# AAS_module_MCU-rev1_2.net
KiCad netlist of a schematic drawn in Altium Designer
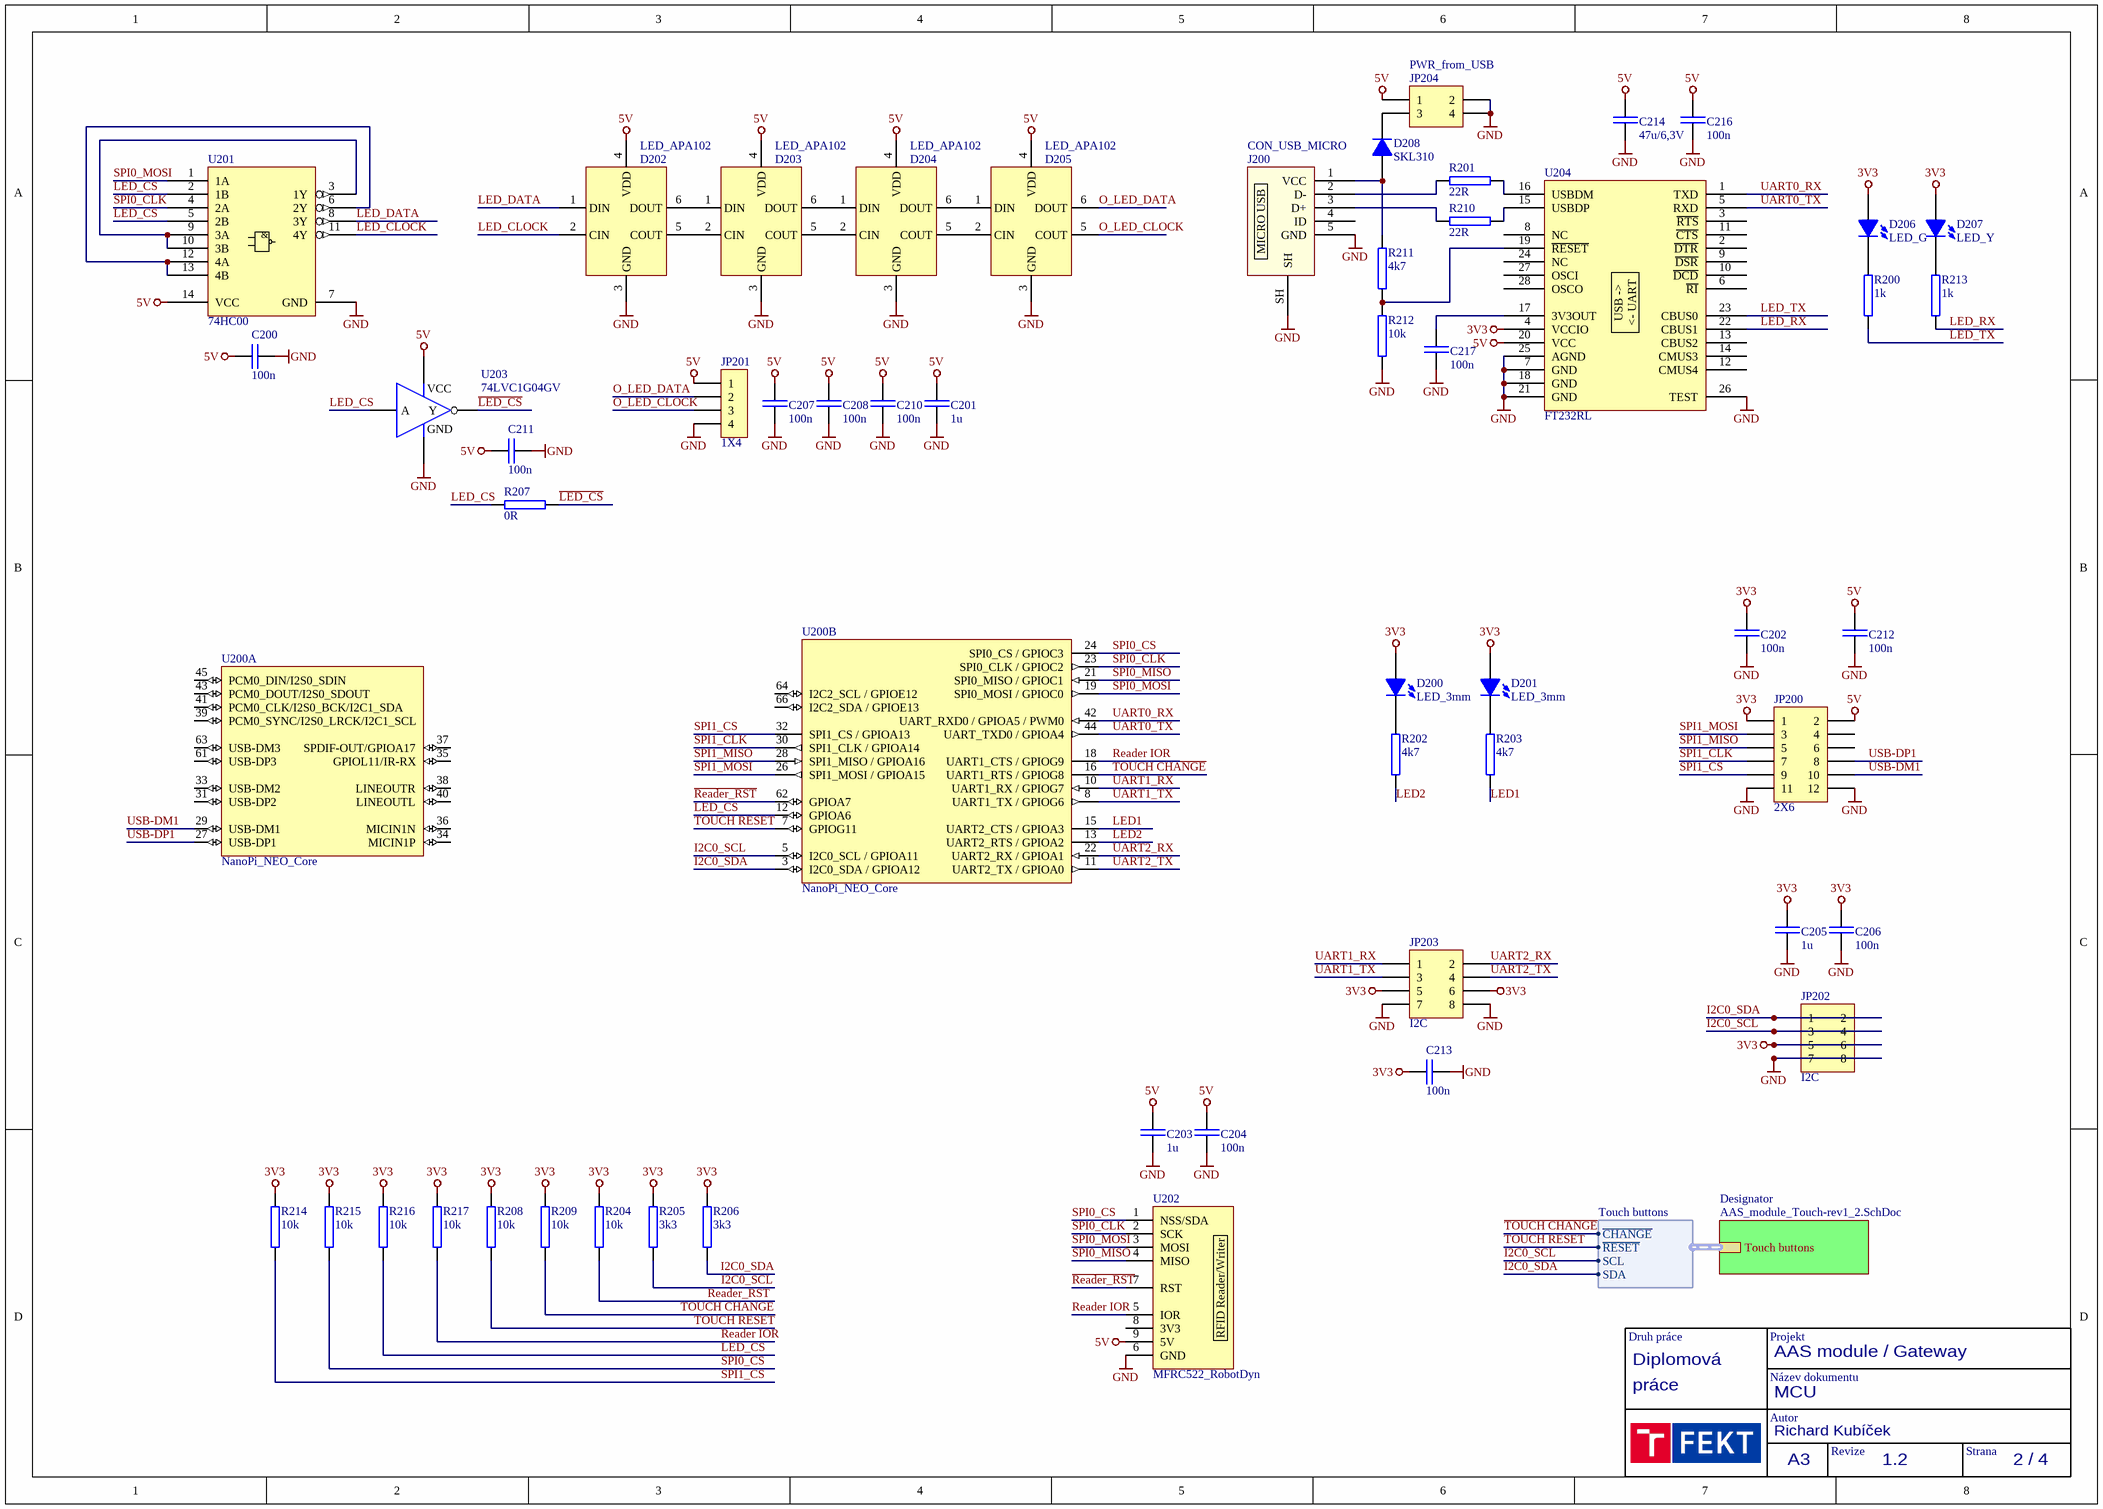
[diagram p0: AAS_module_MCU-rev1_2.SchDoc]

(export (version "E")
  (design (tool "Eeschema 10.0.6"))
  (components
    (comp (ref "C200")
      (value "100n")
      (footprint "C0603")
      (description "Capacitor SMD 0603")
      (libsource (lib "SmartSys") (part "C_0603"))
    )
    (comp (ref "C201")
      (value "1u")
      (footprint "C0603")
      (description "Capacitor SMD 0603")
      (libsource (lib "SmartSys") (part "C_0603"))
    )
    (comp (ref "C202")
      (value "100n")
      (footprint "C0603")
      (description "Capacitor SMD 0603")
      (libsource (lib "SmartSys") (part "C_0603"))
    )
    (comp (ref "C203")
      (value "1u")
      (footprint "C0603")
      (description "Capacitor SMD 0603")
      (libsource (lib "SmartSys") (part "C_0603"))
    )
    (comp (ref "C204")
      (value "100n")
      (footprint "C0603")
      (description "Capacitor SMD 0603")
      (libsource (lib "SmartSys") (part "C_0603"))
    )
    (comp (ref "C205")
      (value "1u")
      (footprint "C0603")
      (description "Capacitor SMD 0603")
      (libsource (lib "SmartSys") (part "C_0603"))
    )
    (comp (ref "C206")
      (value "100n")
      (footprint "C0603")
      (description "Capacitor SMD 0603")
      (libsource (lib "SmartSys") (part "C_0603"))
    )
    (comp (ref "C207")
      (value "100n")
      (footprint "C0603")
      (description "Capacitor SMD 0603")
      (libsource (lib "SmartSys") (part "C_0603"))
    )
    (comp (ref "C208")
      (value "100n")
      (footprint "C0603")
      (description "Capacitor SMD 0603")
      (libsource (lib "SmartSys") (part "C_0603"))
    )
    (comp (ref "C210")
      (value "100n")
      (footprint "C0603")
      (description "Capacitor SMD 0603")
      (libsource (lib "SmartSys") (part "C_0603"))
    )
    (comp (ref "C211")
      (value "100n")
      (footprint "C0603")
      (description "Capacitor SMD 0603")
      (libsource (lib "SmartSys") (part "C_0603"))
    )
    (comp (ref "C212")
      (value "100n")
      (footprint "C0603")
      (description "Capacitor SMD 0603")
      (libsource (lib "SmartSys") (part "C_0603"))
    )
    (comp (ref "C213")
      (value "100n")
      (footprint "C0603")
      (description "Capacitor SMD 0603")
      (libsource (lib "SmartSys") (part "C_0603"))
    )
    (comp (ref "C214")
      (value "47u/6,3V")
      (footprint "C1206")
      (description "Capacitor SMD 1206")
      (libsource (lib "SmartSys") (part "C_1206"))
    )
    (comp (ref "C216")
      (value "100n")
      (footprint "C0603")
      (description "Capacitor SMD 0603")
      (libsource (lib "SmartSys") (part "C_0603"))
    )
    (comp (ref "C217")
      (value "100n")
      (footprint "C0603")
      (description "Capacitor SMD 0603")
      (libsource (lib "SmartSys") (part "C_0603"))
    )
    (comp (ref "D200")
      (value "LED_3mm")
      (footprint "LED_THT_3MM_P2.5_GREEN")
      (description "LED 3mm")
      (libsource (lib "SmartSys") (part "LED_3mm"))
    )
    (comp (ref "D201")
      (value "LED_3mm")
      (footprint "LED_THT_3MM_P2.5_GREEN")
      (description "LED 3mm")
      (libsource (lib "SmartSys") (part "LED_3mm"))
    )
    (comp (ref "D202")
      (value "LED_APA102")
      (footprint "APA102")
      (description "Intelligent control LED integrated light source")
      (libsource (lib "my_parts") (part "LED_APA102"))
    )
    (comp (ref "D203")
      (value "LED_APA102")
      (footprint "APA102")
      (description "Intelligent control LED integrated light source")
      (libsource (lib "my_parts") (part "LED_APA102"))
    )
    (comp (ref "D204")
      (value "LED_APA102")
      (footprint "APA102")
      (description "Intelligent control LED integrated light source")
      (libsource (lib "my_parts") (part "LED_APA102"))
    )
    (comp (ref "D205")
      (value "LED_APA102")
      (footprint "APA102")
      (description "Intelligent control LED integrated light source")
      (libsource (lib "my_parts") (part "LED_APA102"))
    )
    (comp (ref "D206")
      (value "LED_G")
      (footprint "LED_0603")
      (description "LED SMD 0603")
      (libsource (lib "SmartSys") (part "LED_0603"))
    )
    (comp (ref "D207")
      (value "LED_Y")
      (footprint "LED_0603")
      (description "LED SMD 0603")
      (libsource (lib "SmartSys") (part "LED_0603"))
    )
    (comp (ref "D208")
      (value "SKL310")
      (footprint "SOD123")
      (description "Diode")
      (libsource (lib "SmartSys") (part "1N4007"))
    )
    (comp (ref "J200")
      (value "CON_USB_MICRO")
      (footprint "MICRO USB-B SMD")
      (libsource (lib "SmartSys") (part "CON_USB_MICRO"))
    )
    (comp (ref "JP200")
      (value "2X6")
      (footprint "HDR2x6")
      (description "Header, 12-Pin, Dual row")
      (libsource (lib "SmartSys") (part "Header 2X6"))
    )
    (comp (ref "JP201")
      (value "1X4")
      (footprint "HDR1X4")
      (description "Header, 4-Pin, Single row")
      (libsource (lib "SmartSys") (part "Header 1X4"))
    )
    (comp (ref "JP202")
      (value "I2C")
      (footprint "HDR2X4")
      (description "Header, 8-Pin, Dual row")
      (libsource (lib "SmartSys") (part "Header 2X4"))
    )
    (comp (ref "JP203")
      (value "I2C")
      (footprint "HDR2X4")
      (description "Header, 8-Pin, Dual row")
      (libsource (lib "SmartSys") (part "Header 2X4"))
    )
    (comp (ref "JP204")
      (value "PWR_from_USB")
      (footprint "HDR2X2A")
      (description "Header, 6-Pin, Dual row")
      (libsource (lib "SmartSys") (part "Header 2X2"))
    )
    (comp (ref "R200")
      (value "1k")
      (footprint "R0603")
      (description "Resistor SMD 0603")
      (libsource (lib "SmartSys") (part "R_0603"))
    )
    (comp (ref "R201")
      (value "22R")
      (footprint "R0603")
      (description "Resistor SMD 0603")
      (libsource (lib "SmartSys") (part "R_0603"))
    )
    (comp (ref "R202")
      (value "4k7")
      (footprint "R0603")
      (description "Resistor SMD 0603")
      (libsource (lib "SmartSys") (part "R_0603"))
    )
    (comp (ref "R203")
      (value "4k7")
      (footprint "R0603")
      (description "Resistor SMD 0603")
      (libsource (lib "SmartSys") (part "R_0603"))
    )
    (comp (ref "R204")
      (value "10k")
      (footprint "R0603")
      (description "Resistor SMD 0603")
      (libsource (lib "SmartSys") (part "R_0603"))
    )
    (comp (ref "R205")
      (value "3k3")
      (footprint "R0603")
      (description "Resistor SMD 0603")
      (libsource (lib "SmartSys") (part "R_0603"))
    )
    (comp (ref "R206")
      (value "3k3")
      (footprint "R0603")
      (description "Resistor SMD 0603")
      (libsource (lib "SmartSys") (part "R_0603"))
    )
    (comp (ref "R207")
      (value "0R")
      (footprint "R0603")
      (description "Resistor SMD 0603")
      (libsource (lib "SmartSys") (part "R_0603"))
    )
    (comp (ref "R208")
      (value "10k")
      (footprint "R0603")
      (description "Resistor SMD 0603")
      (libsource (lib "SmartSys") (part "R_0603"))
    )
    (comp (ref "R209")
      (value "10k")
      (footprint "R0603")
      (description "Resistor SMD 0603")
      (libsource (lib "SmartSys") (part "R_0603"))
    )
    (comp (ref "R210")
      (value "22R")
      (footprint "R0603")
      (description "Resistor SMD 0603")
      (libsource (lib "SmartSys") (part "R_0603"))
    )
    (comp (ref "R211")
      (value "4k7")
      (footprint "R0603")
      (description "Resistor SMD 0603")
      (libsource (lib "SmartSys") (part "R_0603"))
    )
    (comp (ref "R212")
      (value "10k")
      (footprint "R0603")
      (description "Resistor SMD 0603")
      (libsource (lib "SmartSys") (part "R_0603"))
    )
    (comp (ref "R213")
      (value "1k")
      (footprint "R0603")
      (description "Resistor SMD 0603")
      (libsource (lib "SmartSys") (part "R_0603"))
    )
    (comp (ref "R214")
      (value "10k")
      (footprint "R0603")
      (description "Resistor SMD 0603")
      (libsource (lib "SmartSys") (part "R_0603"))
    )
    (comp (ref "R215")
      (value "10k")
      (footprint "R0603")
      (description "Resistor SMD 0603")
      (libsource (lib "SmartSys") (part "R_0603"))
    )
    (comp (ref "R216")
      (value "10k")
      (footprint "R0603")
      (description "Resistor SMD 0603")
      (libsource (lib "SmartSys") (part "R_0603"))
    )
    (comp (ref "R217")
      (value "10k")
      (footprint "R0603")
      (description "Resistor SMD 0603")
      (libsource (lib "SmartSys") (part "R_0603"))
    )
    (comp (ref "U200")
      (value "NanoPi_NEO_Core")
      (footprint "NanoPi_NEO_Core_right")
      (libsource (lib "my_parts") (part "NanoPi_NEO_Core"))
    )
    (comp (ref "U201")
      (value "74HC00")
      (footprint "SO-14")
      (description "Quad 2-input NAND gate")
      (libsource (lib "my_parts") (part "74HC00"))
    )
    (comp (ref "U202")
      (value "MFRC522_RobotDyn")
      (footprint "MFRC522_RobotDyn")
      (libsource (lib "my_parts") (part "MFRC522_RobotDyn"))
    )
    (comp (ref "U203")
      (value "74LVC1G04GV")
      (footprint "SOT-25")
      (description "Single inverter")
      (libsource (lib "ELEKON") (part "74LVC1G04GV"))
    )
    (comp (ref "U204")
      (value "FT232RL")
      (footprint "SSOP-28")
      (description "USB Interface IC USB to Serial UART Enhanced IC")
      (libsource (lib "my_parts") (part "FT232RL"))
    )
  )
  (nets
    (net (code "3") (name "/I2C0_SCL") (class "Default")
      (node (ref "JP202") (pin "3") (pinfunction "3_3") (pintype "passive"))
      (node (ref "JP202") (pin "4") (pinfunction "4_4") (pintype "passive"))
      (node (ref "R205") (pin "1") (pinfunction "1_1") (pintype "passive"))
      (node (ref "U200") (pin "5") (pinfunction "I2C0_SCL_/_GPIOA11_5") (pintype "bidirectional"))
    )
    (net (code "4") (name "/I2C0_SDA") (class "Default")
      (node (ref "JP202") (pin "1") (pinfunction "1_1") (pintype "passive"))
      (node (ref "JP202") (pin "2") (pinfunction "2_2") (pintype "passive"))
      (node (ref "R206") (pin "1") (pinfunction "1_1") (pintype "passive"))
      (node (ref "U200") (pin "3") (pinfunction "I2C0_SDA_/_GPIOA12_3") (pintype "bidirectional"))
    )
    (net (code "5") (name "/LED1") (class "Default")
      (node (ref "R203") (pin "1") (pinfunction "1_1") (pintype "passive"))
      (node (ref "U200") (pin "15") (pinfunction "UART2_CTS_/_GPIOA3_15") (pintype "passive"))
    )
    (net (code "6") (name "/LED2") (class "Default")
      (node (ref "R202") (pin "1") (pinfunction "1_1") (pintype "passive"))
      (node (ref "U200") (pin "13") (pinfunction "UART2_RTS_/_GPIOA2_13") (pintype "passive"))
    )
    (net (code "7") (name "/LED_CLOCK") (class "Default")
      (node (ref "D202") (pin "2") (pinfunction "CIN_2") (pintype "passive"))
      (node (ref "U201") (pin "11") (pinfunction "4Y_11") (pintype "output"))
    )
    (net (code "8") (name "/LED_CS") (class "Default")
      (node (ref "R207") (pin "2") (pinfunction "2_2") (pintype "passive"))
      (node (ref "R216") (pin "1") (pinfunction "1_1") (pintype "passive"))
      (node (ref "U200") (pin "12") (pinfunction "GPIOA6_12") (pintype "bidirectional"))
      (node (ref "U203") (pin "2") (pinfunction "A_2") (pintype "passive"))
    )
    (net (code "9") (name "/LED_DATA") (class "Default")
      (node (ref "D202") (pin "1") (pinfunction "DIN_1") (pintype "passive"))
      (node (ref "U201") (pin "8") (pinfunction "3Y_8") (pintype "output"))
    )
    (net (code "10") (name "/LED_RX") (class "Default")
      (node (ref "R213") (pin "1") (pinfunction "1_1") (pintype "passive"))
      (node (ref "U204") (pin "22") (pinfunction "CBUS1_22") (pintype "passive"))
    )
    (net (code "11") (name "/LED_TX") (class "Default")
      (node (ref "R200") (pin "1") (pinfunction "1_1") (pintype "passive"))
      (node (ref "U204") (pin "23") (pinfunction "CBUS0_23") (pintype "passive"))
    )
    (net (code "12") (name "/O_LED_CLOCK") (class "Default")
      (node (ref "D205") (pin "5") (pinfunction "COUT_5") (pintype "passive"))
      (node (ref "JP201") (pin "3") (pinfunction "3_3") (pintype "passive"))
    )
    (net (code "13") (name "/O_LED_DATA") (class "Default")
      (node (ref "D205") (pin "6") (pinfunction "DOUT_6") (pintype "passive"))
      (node (ref "JP201") (pin "2") (pinfunction "2_2") (pintype "passive"))
    )
    (net (code "14") (name "/Reader IOR") (class "Default")
      (node (ref "R217") (pin "1") (pinfunction "1_1") (pintype "passive"))
      (node (ref "U200") (pin "18") (pinfunction "UART1_CTS_/_GPIOG9_18") (pintype "passive"))
      (node (ref "U202") (pin "5") (pinfunction "IOR_5") (pintype "passive"))
    )
    (net (code "15") (name "/SPI0_CLK") (class "Default")
      (node (ref "U200") (pin "23") (pinfunction "SPI0_CLK_/_GPIOC2_23") (pintype "output"))
      (node (ref "U201") (pin "4") (pinfunction "2A_4") (pintype "tri_state"))
      (node (ref "U202") (pin "2") (pinfunction "SCK_2") (pintype "passive"))
    )
    (net (code "16") (name "/SPI0_CS") (class "Default")
      (node (ref "R215") (pin "1") (pinfunction "1_1") (pintype "passive"))
      (node (ref "U200") (pin "24") (pinfunction "SPI0_CS_/_GPIOC3_24") (pintype "passive"))
      (node (ref "U202") (pin "1") (pinfunction "NSS/SDA_1") (pintype "passive"))
    )
    (net (code "17") (name "/SPI0_MISO") (class "Default")
      (node (ref "U200") (pin "21") (pinfunction "SPI0_MISO_/_GPIOC1_21") (pintype "input"))
      (node (ref "U202") (pin "4") (pinfunction "MISO_4") (pintype "passive"))
    )
    (net (code "18") (name "/SPI0_MOSI") (class "Default")
      (node (ref "U200") (pin "19") (pinfunction "SPI0_MOSI_/_GPIOC0_19") (pintype "output"))
      (node (ref "U201") (pin "1") (pinfunction "1A_1") (pintype "tri_state"))
      (node (ref "U202") (pin "3") (pinfunction "MOSI_3") (pintype "passive"))
    )
    (net (code "19") (name "/SPI1_CLK") (class "Default")
      (node (ref "JP200") (pin "7") (pinfunction "7_7") (pintype "passive"))
      (node (ref "U200") (pin "30") (pinfunction "SPI1_CLK_/_GPIOA14_30") (pintype "output"))
    )
    (net (code "20") (name "/SPI1_CS") (class "Default")
      (node (ref "JP200") (pin "9") (pinfunction "9_9") (pintype "passive"))
      (node (ref "R214") (pin "1") (pinfunction "1_1") (pintype "passive"))
      (node (ref "U200") (pin "32") (pinfunction "SPI1_CS_/_GPIOA13_32") (pintype "passive"))
    )
    (net (code "21") (name "/SPI1_MISO") (class "Default")
      (node (ref "JP200") (pin "5") (pinfunction "5_5") (pintype "passive"))
      (node (ref "U200") (pin "28") (pinfunction "SPI1_MISO_/_GPIOA16_28") (pintype "input"))
    )
    (net (code "22") (name "/SPI1_MOSI") (class "Default")
      (node (ref "JP200") (pin "3") (pinfunction "3_3") (pintype "passive"))
      (node (ref "U200") (pin "26") (pinfunction "SPI1_MOSI_/_GPIOA15_26") (pintype "output"))
    )
    (net (code "23") (name "/UART0_RX") (class "Default")
      (node (ref "U200") (pin "42") (pinfunction "UART_RXD0_/_GPIOA5_/_PWM0_42") (pintype "input"))
      (node (ref "U204") (pin "1") (pinfunction "TXD_1") (pintype "passive"))
    )
    (net (code "24") (name "/UART0_TX") (class "Default")
      (node (ref "U200") (pin "44") (pinfunction "UART_TXD0_/_GPIOA4_44") (pintype "output"))
      (node (ref "U204") (pin "5") (pinfunction "RXD_5") (pintype "passive"))
    )
    (net (code "25") (name "/UART1_RX") (class "Default")
      (node (ref "JP203") (pin "1") (pinfunction "1_1") (pintype "passive"))
      (node (ref "U200") (pin "10") (pinfunction "UART1_RX_/_GPIOG7_10") (pintype "input"))
    )
    (net (code "26") (name "/UART1_TX") (class "Default")
      (node (ref "JP203") (pin "3") (pinfunction "3_3") (pintype "passive"))
      (node (ref "U200") (pin "8") (pinfunction "UART1_TX_/_GPIOG6_8") (pintype "output"))
    )
    (net (code "27") (name "/UART2_RX") (class "Default")
      (node (ref "JP203") (pin "2") (pinfunction "2_2") (pintype "passive"))
      (node (ref "U200") (pin "22") (pinfunction "UART2_RX_/_GPIOA1_22") (pintype "input"))
    )
    (net (code "28") (name "/UART2_TX") (class "Default")
      (node (ref "JP203") (pin "4") (pinfunction "4_4") (pintype "passive"))
      (node (ref "U200") (pin "11") (pinfunction "UART2_TX_/_GPIOA0_11") (pintype "output"))
    )
    (net (code "29") (name "/USB-DM1") (class "Default")
      (node (ref "JP200") (pin "10") (pinfunction "10_10") (pintype "passive"))
      (node (ref "U200") (pin "29") (pinfunction "USB-DM1_29") (pintype "bidirectional"))
    )
    (net (code "30") (name "/USB-DP1") (class "Default")
      (node (ref "JP200") (pin "8") (pinfunction "8_8") (pintype "passive"))
      (node (ref "U200") (pin "27") (pinfunction "USB-DP1_27") (pintype "bidirectional"))
    )
    (net (code "32") (name "/~{LED_CS}") (class "Default")
      (node (ref "R207") (pin "1") (pinfunction "1_1") (pintype "passive"))
      (node (ref "U201") (pin "2") (pinfunction "1B_2") (pintype "tri_state"))
      (node (ref "U201") (pin "5") (pinfunction "2B_5") (pintype "tri_state"))
      (node (ref "U203") (pin "4") (pinfunction "Y_4") (pintype "passive"))
    )
    (net (code "33") (name "/~{Reader_RST}") (class "Default")
      (node (ref "R204") (pin "1") (pinfunction "1_1") (pintype "passive"))
      (node (ref "U200") (pin "62") (pinfunction "GPIOA7_62") (pintype "bidirectional"))
      (node (ref "U202") (pin "7") (pinfunction "RST_7") (pintype "passive"))
    )
    (net (code "34") (name "/~{TOUCH CHANGE}") (class "Default")
      (node (ref "R209") (pin "1") (pinfunction "1_1") (pintype "passive"))
      (node (ref "U200") (pin "16") (pinfunction "UART1_RTS_/_GPIOG8_16") (pintype "passive"))
    )
    (net (code "35") (name "/~{TOUCH RESET}") (class "Default")
      (node (ref "R208") (pin "1") (pinfunction "1_1") (pintype "passive"))
      (node (ref "U200") (pin "7") (pinfunction "GPIOG11_7") (pintype "bidirectional"))
    )
    (net (code "36") (name "3V3") (class "Default")
      (node (ref "C202") (pin "1") (pinfunction "1_1") (pintype "passive"))
      (node (ref "C205") (pin "1") (pinfunction "1_1") (pintype "passive"))
      (node (ref "C206") (pin "1") (pinfunction "1_1") (pintype "passive"))
      (node (ref "C213") (pin "1") (pinfunction "1_1") (pintype "passive"))
      (node (ref "D200") (pin "A") (pinfunction "A_A") (pintype "passive"))
      (node (ref "D201") (pin "A") (pinfunction "A_A") (pintype "passive"))
      (node (ref "D206") (pin "A") (pinfunction "A_A") (pintype "passive"))
      (node (ref "D207") (pin "A") (pinfunction "A_A") (pintype "passive"))
      (node (ref "JP200") (pin "1") (pinfunction "1_1") (pintype "passive"))
      (node (ref "JP202") (pin "5") (pinfunction "5_5") (pintype "passive"))
      (node (ref "JP202") (pin "6") (pinfunction "6_6") (pintype "passive"))
      (node (ref "JP203") (pin "5") (pinfunction "5_5") (pintype "passive"))
      (node (ref "JP203") (pin "6") (pinfunction "6_6") (pintype "passive"))
      (node (ref "R204") (pin "2") (pinfunction "2_2") (pintype "passive"))
      (node (ref "R205") (pin "2") (pinfunction "2_2") (pintype "passive"))
      (node (ref "R206") (pin "2") (pinfunction "2_2") (pintype "passive"))
      (node (ref "R208") (pin "2") (pinfunction "2_2") (pintype "passive"))
      (node (ref "R209") (pin "2") (pinfunction "2_2") (pintype "passive"))
      (node (ref "R214") (pin "2") (pinfunction "2_2") (pintype "passive"))
      (node (ref "R215") (pin "2") (pinfunction "2_2") (pintype "passive"))
      (node (ref "R216") (pin "2") (pinfunction "2_2") (pintype "passive"))
      (node (ref "R217") (pin "2") (pinfunction "2_2") (pintype "passive"))
      (node (ref "U204") (pin "4") (pinfunction "VCCIO_4") (pintype "passive"))
    )
    (net (code "37") (name "5V") (class "Default")
      (node (ref "C200") (pin "1") (pinfunction "1_1") (pintype "passive"))
      (node (ref "C201") (pin "1") (pinfunction "1_1") (pintype "passive"))
      (node (ref "C203") (pin "1") (pinfunction "1_1") (pintype "passive"))
      (node (ref "C204") (pin "1") (pinfunction "1_1") (pintype "passive"))
      (node (ref "C207") (pin "1") (pinfunction "1_1") (pintype "passive"))
      (node (ref "C208") (pin "1") (pinfunction "1_1") (pintype "passive"))
      (node (ref "C210") (pin "1") (pinfunction "1_1") (pintype "passive"))
      (node (ref "C211") (pin "1") (pinfunction "1_1") (pintype "passive"))
      (node (ref "C212") (pin "1") (pinfunction "1_1") (pintype "passive"))
      (node (ref "C214") (pin "1") (pinfunction "1_1") (pintype "passive"))
      (node (ref "C216") (pin "2") (pinfunction "2_2") (pintype "passive"))
      (node (ref "D202") (pin "4") (pinfunction "VDD_4") (pintype "passive"))
      (node (ref "D203") (pin "4") (pinfunction "VDD_4") (pintype "passive"))
      (node (ref "D204") (pin "4") (pinfunction "VDD_4") (pintype "passive"))
      (node (ref "D205") (pin "4") (pinfunction "VDD_4") (pintype "passive"))
      (node (ref "JP200") (pin "2") (pinfunction "2_2") (pintype "passive"))
      (node (ref "JP201") (pin "1") (pinfunction "1_1") (pintype "passive"))
      (node (ref "JP204") (pin "1") (pinfunction "1_1") (pintype "passive"))
      (node (ref "U201") (pin "14") (pinfunction "VCC_14") (pintype "power_in"))
      (node (ref "U202") (pin "9") (pinfunction "5V_9") (pintype "passive"))
      (node (ref "U203") (pin "5") (pinfunction "VCC_5") (pintype "power_in"))
      (node (ref "U204") (pin "20") (pinfunction "VCC_20") (pintype "passive"))
    )
    (net (code "38") (name "GND") (class "Default")
      (node (ref "C200") (pin "2") (pinfunction "2_2") (pintype "passive"))
      (node (ref "C201") (pin "2") (pinfunction "2_2") (pintype "passive"))
      (node (ref "C202") (pin "2") (pinfunction "2_2") (pintype "passive"))
      (node (ref "C203") (pin "2") (pinfunction "2_2") (pintype "passive"))
      (node (ref "C204") (pin "2") (pinfunction "2_2") (pintype "passive"))
      (node (ref "C205") (pin "2") (pinfunction "2_2") (pintype "passive"))
      (node (ref "C206") (pin "2") (pinfunction "2_2") (pintype "passive"))
      (node (ref "C207") (pin "2") (pinfunction "2_2") (pintype "passive"))
      (node (ref "C208") (pin "2") (pinfunction "2_2") (pintype "passive"))
      (node (ref "C210") (pin "2") (pinfunction "2_2") (pintype "passive"))
      (node (ref "C211") (pin "2") (pinfunction "2_2") (pintype "passive"))
      (node (ref "C212") (pin "2") (pinfunction "2_2") (pintype "passive"))
      (node (ref "C213") (pin "2") (pinfunction "2_2") (pintype "passive"))
      (node (ref "C214") (pin "2") (pinfunction "2_2") (pintype "passive"))
      (node (ref "C216") (pin "1") (pinfunction "1_1") (pintype "passive"))
      (node (ref "C217") (pin "1") (pinfunction "1_1") (pintype "passive"))
      (node (ref "D202") (pin "3") (pinfunction "GND_3") (pintype "passive"))
      (node (ref "D203") (pin "3") (pinfunction "GND_3") (pintype "passive"))
      (node (ref "D204") (pin "3") (pinfunction "GND_3") (pintype "passive"))
      (node (ref "D205") (pin "3") (pinfunction "GND_3") (pintype "passive"))
      (node (ref "J200") (pin "5") (pinfunction "GND_5") (pintype "passive"))
      (node (ref "J200") (pin "SH") (pinfunction "SH_SH") (pintype "passive"))
      (node (ref "JP200") (pin "11") (pinfunction "11_11") (pintype "passive"))
      (node (ref "JP200") (pin "12") (pinfunction "12_12") (pintype "passive"))
      (node (ref "JP201") (pin "4") (pinfunction "4_4") (pintype "passive"))
      (node (ref "JP202") (pin "7") (pinfunction "7_7") (pintype "passive"))
      (node (ref "JP202") (pin "8") (pinfunction "8_8") (pintype "passive"))
      (node (ref "JP203") (pin "7") (pinfunction "7_7") (pintype "passive"))
      (node (ref "JP203") (pin "8") (pinfunction "8_8") (pintype "passive"))
      (node (ref "JP204") (pin "2") (pinfunction "2_2") (pintype "passive"))
      (node (ref "JP204") (pin "4") (pinfunction "4_4") (pintype "passive"))
      (node (ref "R212") (pin "2") (pinfunction "2_2") (pintype "passive"))
      (node (ref "U201") (pin "7") (pinfunction "GND_7") (pintype "passive"))
      (node (ref "U202") (pin "6") (pinfunction "GND_6") (pintype "passive"))
      (node (ref "U203") (pin "3") (pinfunction "GND_3") (pintype "power_in"))
      (node (ref "U204") (pin "18") (pinfunction "GND_18") (pintype "passive"))
      (node (ref "U204") (pin "21") (pinfunction "GND_21") (pintype "passive"))
      (node (ref "U204") (pin "25") (pinfunction "AGND_25") (pintype "passive"))
      (node (ref "U204") (pin "26") (pinfunction "TEST_26") (pintype "passive"))
      (node (ref "U204") (pin "7") (pinfunction "GND_7") (pintype "passive"))
    )
    (net (code "39") (name "Net-(D200-PadK)") (class "Default")
      (node (ref "D200") (pin "K") (pinfunction "K_K") (pintype "passive"))
      (node (ref "R202") (pin "2") (pinfunction "2_2") (pintype "passive"))
    )
    (net (code "40") (name "Net-(D201-PadK)") (class "Default")
      (node (ref "D201") (pin "K") (pinfunction "K_K") (pintype "passive"))
      (node (ref "R203") (pin "2") (pinfunction "2_2") (pintype "passive"))
    )
    (net (code "41") (name "Net-(D202-COUT)") (class "Default")
      (node (ref "D202") (pin "5") (pinfunction "COUT_5") (pintype "passive"))
      (node (ref "D203") (pin "2") (pinfunction "CIN_2") (pintype "passive"))
    )
    (net (code "42") (name "Net-(D202-DOUT)") (class "Default")
      (node (ref "D202") (pin "6") (pinfunction "DOUT_6") (pintype "passive"))
      (node (ref "D203") (pin "1") (pinfunction "DIN_1") (pintype "passive"))
    )
    (net (code "43") (name "Net-(D203-COUT)") (class "Default")
      (node (ref "D203") (pin "5") (pinfunction "COUT_5") (pintype "passive"))
      (node (ref "D204") (pin "2") (pinfunction "CIN_2") (pintype "passive"))
    )
    (net (code "44") (name "Net-(D203-DOUT)") (class "Default")
      (node (ref "D203") (pin "6") (pinfunction "DOUT_6") (pintype "passive"))
      (node (ref "D204") (pin "1") (pinfunction "DIN_1") (pintype "passive"))
    )
    (net (code "45") (name "Net-(D204-COUT)") (class "Default")
      (node (ref "D204") (pin "5") (pinfunction "COUT_5") (pintype "passive"))
      (node (ref "D205") (pin "2") (pinfunction "CIN_2") (pintype "passive"))
    )
    (net (code "46") (name "Net-(D204-DOUT)") (class "Default")
      (node (ref "D204") (pin "6") (pinfunction "DOUT_6") (pintype "passive"))
      (node (ref "D205") (pin "1") (pinfunction "DIN_1") (pintype "passive"))
    )
    (net (code "47") (name "Net-(D206-PadK)") (class "Default")
      (node (ref "D206") (pin "K") (pinfunction "K_K") (pintype "passive"))
      (node (ref "R200") (pin "2") (pinfunction "2_2") (pintype "passive"))
    )
    (net (code "48") (name "Net-(D207-PadK)") (class "Default")
      (node (ref "D207") (pin "K") (pinfunction "K_K") (pintype "passive"))
      (node (ref "R213") (pin "2") (pinfunction "2_2") (pintype "passive"))
    )
    (net (code "49") (name "Net-(D208-PadK)") (class "Default")
      (node (ref "D208") (pin "K") (pinfunction "K_K") (pintype "passive"))
      (node (ref "JP204") (pin "3") (pinfunction "3_3") (pintype "passive"))
    )
    (net (code "50") (name "Net-(J200-D+)") (class "Default")
      (node (ref "J200") (pin "3") (pinfunction "D+_3") (pintype "passive"))
      (node (ref "R210") (pin "1") (pinfunction "1_1") (pintype "passive"))
    )
    (net (code "51") (name "Net-(J200-D-)") (class "Default")
      (node (ref "J200") (pin "2") (pinfunction "D-_2") (pintype "passive"))
      (node (ref "R201") (pin "1") (pinfunction "1_1") (pintype "passive"))
    )
    (net (code "52") (name "Net-(J200-VCC)") (class "Default")
      (node (ref "D208") (pin "A") (pinfunction "A_A") (pintype "passive"))
      (node (ref "J200") (pin "1") (pinfunction "VCC_1") (pintype "passive"))
      (node (ref "R211") (pin "1") (pinfunction "1_1") (pintype "passive"))
    )
    (net (code "53") (name "Net-(U201-1Y)") (class "Default")
      (node (ref "U201") (pin "10") (pinfunction "3B_10") (pintype "tri_state"))
      (node (ref "U201") (pin "3") (pinfunction "1Y_3") (pintype "output"))
      (node (ref "U201") (pin "9") (pinfunction "3A_9") (pintype "tri_state"))
    )
    (net (code "54") (name "Net-(U201-2Y)") (class "Default")
      (node (ref "U201") (pin "12") (pinfunction "4A_12") (pintype "tri_state"))
      (node (ref "U201") (pin "13") (pinfunction "4B_13") (pintype "tri_state"))
      (node (ref "U201") (pin "6") (pinfunction "2Y_6") (pintype "output"))
    )
    (net (code "55") (name "Net-(U204-3V3OUT)") (class "Default")
      (node (ref "C217") (pin "2") (pinfunction "2_2") (pintype "passive"))
      (node (ref "U204") (pin "17") (pinfunction "3V3OUT_17") (pintype "passive"))
    )
    (net (code "56") (name "Net-(U204-USBDM)") (class "Default")
      (node (ref "R201") (pin "2") (pinfunction "2_2") (pintype "passive"))
      (node (ref "U204") (pin "16") (pinfunction "USBDM_16") (pintype "passive"))
    )
    (net (code "57") (name "Net-(U204-USBDP)") (class "Default")
      (node (ref "R210") (pin "2") (pinfunction "2_2") (pintype "passive"))
      (node (ref "U204") (pin "15") (pinfunction "USBDP_15") (pintype "passive"))
    )
    (net (code "58") (name "Net-(U204-~{RESET})") (class "Default")
      (node (ref "R211") (pin "2") (pinfunction "2_2") (pintype "passive"))
      (node (ref "R212") (pin "1") (pinfunction "1_1") (pintype "passive"))
      (node (ref "U204") (pin "19") (pinfunction "~{RESET}_19") (pintype "passive"))
    )
    (net (code "59") (name "unconnected-(J200-ID-Pad4)") (class "Default")
      (node (ref "J200") (pin "4") (pinfunction "ID_4") (pintype "passive"))
    )
    (net (code "60") (name "unconnected-(JP200-Pad4)") (class "Default")
      (node (ref "JP200") (pin "4") (pinfunction "4_4") (pintype "passive"))
    )
    (net (code "61") (name "unconnected-(JP200-Pad6)") (class "Default")
      (node (ref "JP200") (pin "6") (pinfunction "6_6") (pintype "passive"))
    )
    (net (code "62") (name "unconnected-(U200A-GPIOL11{slash}IR-RX-Pad35)") (class "Default")
      (node (ref "U200") (pin "35") (pinfunction "GPIOL11/IR-RX_35") (pintype "bidirectional"))
    )
    (net (code "63") (name "unconnected-(U200A-LINEOUTL-Pad40)") (class "Default")
      (node (ref "U200") (pin "40") (pinfunction "LINEOUTL_40") (pintype "bidirectional"))
    )
    (net (code "64") (name "unconnected-(U200A-LINEOUTR-Pad38)") (class "Default")
      (node (ref "U200") (pin "38") (pinfunction "LINEOUTR_38") (pintype "bidirectional"))
    )
    (net (code "65") (name "unconnected-(U200A-MICIN1N-Pad36)") (class "Default")
      (node (ref "U200") (pin "36") (pinfunction "MICIN1N_36") (pintype "bidirectional"))
    )
    (net (code "66") (name "unconnected-(U200A-MICIN1P-Pad34)") (class "Default")
      (node (ref "U200") (pin "34") (pinfunction "MICIN1P_34") (pintype "bidirectional"))
    )
    (net (code "67") (name "unconnected-(U200A-PCM0_CLK{slash}I2S0_BCK{slash}I2C1_SDA-Pad41)") (class "Default")
      (node (ref "U200") (pin "41") (pinfunction "PCM0_CLK/I2S0_BCK/I2C1_SDA_41") (pintype "bidirectional"))
    )
    (net (code "68") (name "unconnected-(U200A-PCM0_DIN{slash}I2S0_SDIN-Pad45)") (class "Default")
      (node (ref "U200") (pin "45") (pinfunction "PCM0_DIN/I2S0_SDIN_45") (pintype "bidirectional"))
    )
    (net (code "69") (name "unconnected-(U200A-PCM0_DOUT{slash}I2S0_SDOUT-Pad43)") (class "Default")
      (node (ref "U200") (pin "43") (pinfunction "PCM0_DOUT/I2S0_SDOUT_43") (pintype "bidirectional"))
    )
    (net (code "70") (name "unconnected-(U200A-PCM0_SYNC{slash}I2S0_LRCK{slash}I2C1_SCL-Pad39)") (class "Default")
      (node (ref "U200") (pin "39") (pinfunction "PCM0_SYNC/I2S0_LRCK/I2C1_SCL_39") (pintype "bidirectional"))
    )
    (net (code "71") (name "unconnected-(U200A-SPDIF-OUT{slash}GPIOA17-Pad37)") (class "Default")
      (node (ref "U200") (pin "37") (pinfunction "SPDIF-OUT/GPIOA17_37") (pintype "bidirectional"))
    )
    (net (code "72") (name "unconnected-(U200A-USB-DM2-Pad33)") (class "Default")
      (node (ref "U200") (pin "33") (pinfunction "USB-DM2_33") (pintype "bidirectional"))
    )
    (net (code "73") (name "unconnected-(U200A-USB-DM3-Pad63)") (class "Default")
      (node (ref "U200") (pin "63") (pinfunction "USB-DM3_63") (pintype "bidirectional"))
    )
    (net (code "74") (name "unconnected-(U200A-USB-DP2-Pad31)") (class "Default")
      (node (ref "U200") (pin "31") (pinfunction "USB-DP2_31") (pintype "bidirectional"))
    )
    (net (code "75") (name "unconnected-(U200A-USB-DP3-Pad61)") (class "Default")
      (node (ref "U200") (pin "61") (pinfunction "USB-DP3_61") (pintype "bidirectional"))
    )
    (net (code "76") (name "unconnected-(U200B-I2C2_SCL_{slash}_GPIOE12-Pad64)") (class "Default")
      (node (ref "U200") (pin "64") (pinfunction "I2C2_SCL_/_GPIOE12_64") (pintype "bidirectional"))
    )
    (net (code "77") (name "unconnected-(U200B-I2C2_SDA_{slash}_GPIOE13-Pad66)") (class "Default")
      (node (ref "U200") (pin "66") (pinfunction "I2C2_SDA_/_GPIOE13_66") (pintype "bidirectional"))
    )
    (net (code "78") (name "unconnected-(U202-3V3-Pad8)") (class "Default")
      (node (ref "U202") (pin "8") (pinfunction "3V3_8") (pintype "passive"))
    )
    (net (code "79") (name "unconnected-(U203-NC-Pad1)") (class "Default")
      (node (ref "U203") (pin "1") (pinfunction "NC_1") (pintype "passive"))
    )
    (net (code "80") (name "unconnected-(U204-CBUS2-Pad13)") (class "Default")
      (node (ref "U204") (pin "13") (pinfunction "CBUS2_13") (pintype "passive"))
    )
    (net (code "81") (name "unconnected-(U204-CMUS3-Pad14)") (class "Default")
      (node (ref "U204") (pin "14") (pinfunction "CMUS3_14") (pintype "passive"))
    )
    (net (code "82") (name "unconnected-(U204-CMUS4-Pad12)") (class "Default")
      (node (ref "U204") (pin "12") (pinfunction "CMUS4_12") (pintype "passive"))
    )
    (net (code "83") (name "unconnected-(U204-NC-Pad8)") (class "Default")
      (node (ref "U204") (pin "8") (pinfunction "NC_8") (pintype "passive"))
    )
    (net (code "84") (name "unconnected-(U204-NC-Pad24)") (class "Default")
      (node (ref "U204") (pin "24") (pinfunction "NC_24") (pintype "passive"))
    )
    (net (code "85") (name "unconnected-(U204-OSCI-Pad27)") (class "Default")
      (node (ref "U204") (pin "27") (pinfunction "OSCI_27") (pintype "passive"))
    )
    (net (code "86") (name "unconnected-(U204-OSCO-Pad28)") (class "Default")
      (node (ref "U204") (pin "28") (pinfunction "OSCO_28") (pintype "passive"))
    )
    (net (code "87") (name "unconnected-(U204-~{CTS}-Pad11)") (class "Default")
      (node (ref "U204") (pin "11") (pinfunction "~{CTS}_11") (pintype "passive"))
    )
    (net (code "88") (name "unconnected-(U204-~{DCD}-Pad10)") (class "Default")
      (node (ref "U204") (pin "10") (pinfunction "~{DCD}_10") (pintype "passive"))
    )
    (net (code "89") (name "unconnected-(U204-~{DSR}-Pad9)") (class "Default")
      (node (ref "U204") (pin "9") (pinfunction "~{DSR}_9") (pintype "passive"))
    )
    (net (code "90") (name "unconnected-(U204-~{DTR}-Pad2)") (class "Default")
      (node (ref "U204") (pin "2") (pinfunction "~{DTR}_2") (pintype "passive"))
    )
    (net (code "91") (name "unconnected-(U204-~{RI}-Pad6)") (class "Default")
      (node (ref "U204") (pin "6") (pinfunction "~{RI}_6") (pintype "passive"))
    )
    (net (code "92") (name "unconnected-(U204-~{RTS}-Pad3)") (class "Default")
      (node (ref "U204") (pin "3") (pinfunction "~{RTS}_3") (pintype "passive"))
    )
  )
)
